# mbed_to_ccs.net
KiCad netlist of a schematic drawn in Altium Designer
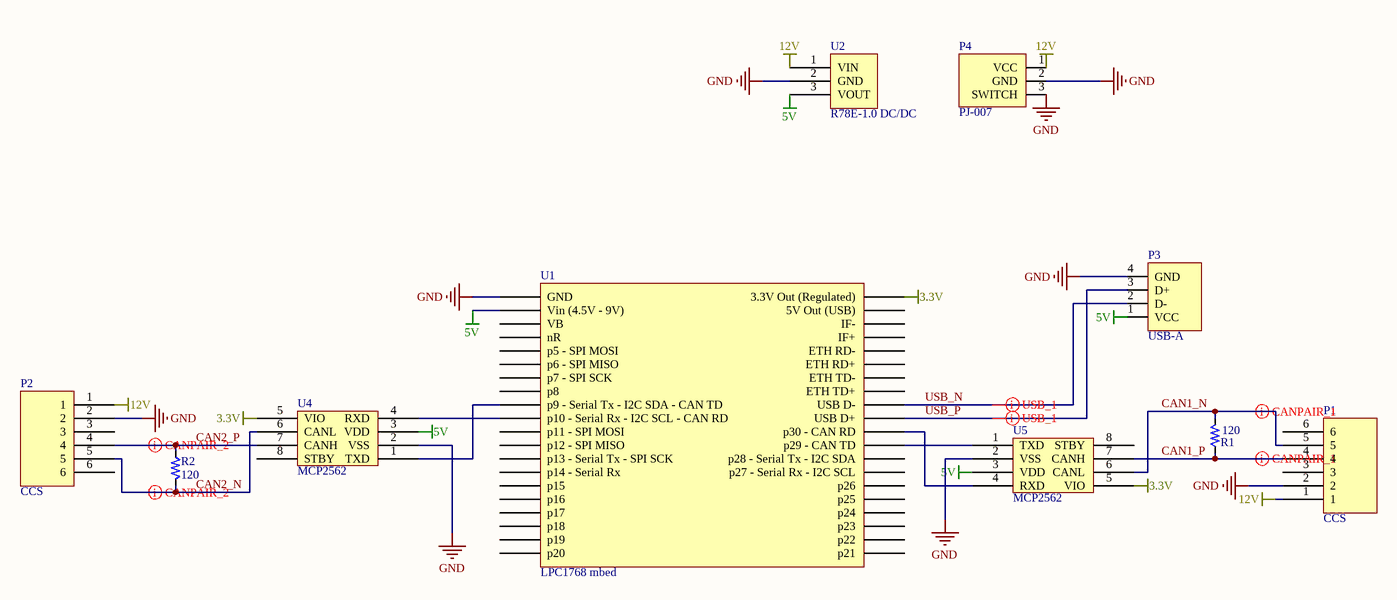
[diagram p0: mbed_to_ccs.SchDoc]

(export (version "E")
  (design (tool "Eeschema 10.0.6"))
  (components
    (comp (ref "P1")
      (value "CCS")
      (footprint "PCB_MLX_MICROFIT_3X2")
      (libsource (lib "") (part "SCH_MLX_MICROFIT_3X2_1"))
    )
    (comp (ref "P2")
      (value "CCS")
      (footprint "PCB_MLX_MICROFIT_3X2")
      (libsource (lib "SCH_MLX_MICROFIT_3X2_P") (part "SCH_MLX_MICROFIT_3X2"))
    )
    (comp (ref "P3")
      (value "USB-A")
      (footprint "USB-A UE27AC54100 Receptacle")
      (libsource (lib "USB-A UE27AC54100 Receptacle") (part "USB-A UE27AC54100 Receptacle"))
    )
    (comp (ref "P4")
      (value "PJ-007")
      (footprint "BARREL JACK PJ007")
      (libsource (lib "BARREL JACK PJ-007") (part "Component_1"))
    )
    (comp (ref "R1")
      (value "120")
      (footprint "PCB_GENERIC_SMD_0603")
      (description "120 Ohms")
      (libsource (lib "SCH_GENERIC_RESISTOR_0603") (part "SCH_GENERIC_RESISTOR_0603"))
    )
    (comp (ref "R2")
      (value "120")
      (footprint "PCB_GENERIC_SMD_0603")
      (description "120 Ohms")
      (libsource (lib "SCH_GENERIC_RESISTOR_0603") (part "SCH_GENERIC_RESISTOR_0603"))
    )
    (comp (ref "U1")
      (value "LPC1768 mbed")
      (footprint "LPC 1768 mbed Layout")
      (libsource (lib "LPC1768_mbed_SCH") (part "LPC1768 mbed"))
    )
    (comp (ref "U2")
      (value "R78E-1.0 DC/DC")
      (footprint "R78-1.0")
      (libsource (lib "R78E-1.0_DCDC_SCH") (part "R78E-1.0"))
    )
    (comp (ref "U4") (value "MCP2562") (footprint "MCP2562") (libsource (lib "") (part "MCP2562_1")))
    (comp (ref "U5") (value "MCP2562") (footprint "MCP2562") (libsource (lib "MCP2562_SCH") (part "MCP2562")))
  )
  (nets
    (net (code "1") (name "/CAN1_N") (class "Default")
      (node (ref "P1") (pin "5") (pinfunction "5_5") (pintype "passive"))
      (node (ref "R1") (pin "2") (pinfunction "2_2") (pintype "passive"))
      (node (ref "U5") (pin "6") (pinfunction "CANL_6") (pintype "passive"))
    )
    (net (code "2") (name "/CAN1_P") (class "Default")
      (node (ref "P1") (pin "4") (pinfunction "4_4") (pintype "passive"))
      (node (ref "R1") (pin "1") (pinfunction "1_1") (pintype "passive"))
      (node (ref "U5") (pin "7") (pinfunction "CANH_7") (pintype "passive"))
    )
    (net (code "3") (name "/CAN2_N") (class "Default")
      (node (ref "P2") (pin "5") (pinfunction "5_5") (pintype "passive"))
      (node (ref "R2") (pin "2") (pinfunction "2_2") (pintype "passive"))
      (node (ref "U4") (pin "6") (pinfunction "CANL_6") (pintype "passive"))
    )
    (net (code "4") (name "/CAN2_P") (class "Default")
      (node (ref "P2") (pin "4") (pinfunction "4_4") (pintype "passive"))
      (node (ref "R2") (pin "1") (pinfunction "1_1") (pintype "passive"))
      (node (ref "U4") (pin "7") (pinfunction "CANH_7") (pintype "passive"))
    )
    (net (code "5") (name "/USB_N") (class "Default")
      (node (ref "P3") (pin "2") (pinfunction "D-_2") (pintype "passive"))
      (node (ref "U1") (pin "32") (pinfunction "USB_D-_32") (pintype "passive"))
    )
    (net (code "6") (name "/USB_P") (class "Default")
      (node (ref "P3") (pin "3") (pinfunction "D+_3") (pintype "passive"))
      (node (ref "U1") (pin "31") (pinfunction "USB_D+_31") (pintype "passive"))
    )
    (net (code "7") (name "3.3V") (class "Default")
      (node (ref "U1") (pin "40") (pinfunction "3.3V_Out_(Regulated)_40") (pintype "passive"))
      (node (ref "U4") (pin "5") (pinfunction "VIO_5") (pintype "passive"))
      (node (ref "U5") (pin "5") (pinfunction "VIO_5") (pintype "passive"))
    )
    (net (code "8") (name "5V") (class "Default")
      (node (ref "P3") (pin "1") (pinfunction "VCC_1") (pintype "passive"))
      (node (ref "U1") (pin "2") (pinfunction "Vin_(4.5V_-_9V)_2") (pintype "passive"))
      (node (ref "U2") (pin "3") (pinfunction "VOUT_3") (pintype "passive"))
      (node (ref "U4") (pin "3") (pinfunction "VDD_3") (pintype "passive"))
      (node (ref "U5") (pin "3") (pinfunction "VDD_3") (pintype "passive"))
    )
    (net (code "9") (name "12V") (class "Default")
      (node (ref "P1") (pin "1") (pinfunction "1_1") (pintype "passive"))
      (node (ref "P2") (pin "1") (pinfunction "1_1") (pintype "passive"))
      (node (ref "P4") (pin "1") (pinfunction "VCC_1") (pintype "passive"))
      (node (ref "U2") (pin "1") (pinfunction "VIN_1") (pintype "passive"))
    )
    (net (code "10") (name "GND") (class "Default")
      (node (ref "P1") (pin "2") (pinfunction "2_2") (pintype "passive"))
      (node (ref "P2") (pin "2") (pinfunction "2_2") (pintype "passive"))
      (node (ref "P3") (pin "4") (pinfunction "GND_4") (pintype "passive"))
      (node (ref "P4") (pin "2") (pinfunction "GND_2") (pintype "passive"))
      (node (ref "P4") (pin "3") (pinfunction "SWITCH_3") (pintype "passive"))
      (node (ref "U1") (pin "1") (pinfunction "GND_1") (pintype "passive"))
      (node (ref "U2") (pin "2") (pinfunction "GND_2") (pintype "passive"))
      (node (ref "U4") (pin "2") (pinfunction "VSS_2") (pintype "passive"))
      (node (ref "U5") (pin "2") (pinfunction "VSS_2") (pintype "passive"))
    )
    (net (code "11") (name "Net-(U1-p9_-_Serial_Tx_-_I2C_SDA_-_CAN_TD)") (class "Default")
      (node (ref "U1") (pin "9") (pinfunction "p9_-_Serial_Tx_-_I2C_SDA_-_CAN_TD_9") (pintype "passive"))
      (node (ref "U4") (pin "1") (pinfunction "TXD_1") (pintype "passive"))
    )
    (net (code "12") (name "Net-(U1-p10_-_Serial_Rx_-_I2C_SCL_-_CAN_RD)") (class "Default")
      (node (ref "U1") (pin "10") (pinfunction "p10_-_Serial_Rx_-_I2C_SCL_-_CAN_RD_10") (pintype "passive"))
      (node (ref "U4") (pin "4") (pinfunction "RXD_4") (pintype "passive"))
    )
    (net (code "13") (name "Net-(U1-p29_-_CAN_TD)") (class "Default")
      (node (ref "U1") (pin "29") (pinfunction "p29_-_CAN_TD_29") (pintype "passive"))
      (node (ref "U5") (pin "1") (pinfunction "TXD_1") (pintype "passive"))
    )
    (net (code "14") (name "Net-(U1-p30_-_CAN_RD)") (class "Default")
      (node (ref "U1") (pin "30") (pinfunction "p30_-_CAN_RD_30") (pintype "passive"))
      (node (ref "U5") (pin "4") (pinfunction "RXD_4") (pintype "passive"))
    )
    (net (code "15") (name "unconnected-(P1-Pad3)") (class "Default")
      (node (ref "P1") (pin "3") (pinfunction "3_3") (pintype "passive"))
    )
    (net (code "16") (name "unconnected-(P1-Pad6)") (class "Default")
      (node (ref "P1") (pin "6") (pinfunction "6_6") (pintype "passive"))
    )
    (net (code "17") (name "unconnected-(P2-Pad3)") (class "Default")
      (node (ref "P2") (pin "3") (pinfunction "3_3") (pintype "passive"))
    )
    (net (code "18") (name "unconnected-(P2-Pad6)") (class "Default")
      (node (ref "P2") (pin "6") (pinfunction "6_6") (pintype "passive"))
    )
    (net (code "19") (name "unconnected-(U1-5V_Out_(USB)-Pad39)") (class "Default")
      (node (ref "U1") (pin "39") (pinfunction "5V_Out_(USB)_39") (pintype "passive"))
    )
    (net (code "20") (name "unconnected-(U1-ETH_RD+-Pad35)") (class "Default")
      (node (ref "U1") (pin "35") (pinfunction "ETH_RD+_35") (pintype "passive"))
    )
    (net (code "21") (name "unconnected-(U1-ETH_RD--Pad36)") (class "Default")
      (node (ref "U1") (pin "36") (pinfunction "ETH_RD-_36") (pintype "passive"))
    )
    (net (code "22") (name "unconnected-(U1-ETH_TD+-Pad33)") (class "Default")
      (node (ref "U1") (pin "33") (pinfunction "ETH_TD+_33") (pintype "passive"))
    )
    (net (code "23") (name "unconnected-(U1-ETH_TD--Pad34)") (class "Default")
      (node (ref "U1") (pin "34") (pinfunction "ETH_TD-_34") (pintype "passive"))
    )
    (net (code "24") (name "unconnected-(U1-IF+-Pad37)") (class "Default")
      (node (ref "U1") (pin "37") (pinfunction "IF+_37") (pintype "passive"))
    )
    (net (code "25") (name "unconnected-(U1-IF--Pad38)") (class "Default")
      (node (ref "U1") (pin "38") (pinfunction "IF-_38") (pintype "passive"))
    )
    (net (code "26") (name "unconnected-(U1-VB-Pad3)") (class "Default")
      (node (ref "U1") (pin "3") (pinfunction "VB_3") (pintype "passive"))
    )
    (net (code "27") (name "unconnected-(U1-nR-Pad4)") (class "Default")
      (node (ref "U1") (pin "4") (pinfunction "nR_4") (pintype "passive"))
    )
    (net (code "28") (name "unconnected-(U1-p5_-_SPI_MOSI-Pad5)") (class "Default")
      (node (ref "U1") (pin "5") (pinfunction "p5_-_SPI_MOSI_5") (pintype "passive"))
    )
    (net (code "29") (name "unconnected-(U1-p6_-_SPI_MISO-Pad6)") (class "Default")
      (node (ref "U1") (pin "6") (pinfunction "p6_-_SPI_MISO_6") (pintype "passive"))
    )
    (net (code "30") (name "unconnected-(U1-p7_-_SPI_SCK-Pad7)") (class "Default")
      (node (ref "U1") (pin "7") (pinfunction "p7_-_SPI_SCK_7") (pintype "passive"))
    )
    (net (code "31") (name "unconnected-(U1-p8-Pad8)") (class "Default")
      (node (ref "U1") (pin "8") (pinfunction "p8_8") (pintype "passive"))
    )
    (net (code "32") (name "unconnected-(U1-p11_-_SPI_MOSI-Pad11)") (class "Default")
      (node (ref "U1") (pin "11") (pinfunction "p11_-_SPI_MOSI_11") (pintype "passive"))
    )
    (net (code "33") (name "unconnected-(U1-p12_-_SPI_MISO-Pad12)") (class "Default")
      (node (ref "U1") (pin "12") (pinfunction "p12_-_SPI_MISO_12") (pintype "passive"))
    )
    (net (code "34") (name "unconnected-(U1-p13_-_Serial_Tx_-_SPI_SCK-Pad13)") (class "Default")
      (node (ref "U1") (pin "13") (pinfunction "p13_-_Serial_Tx_-_SPI_SCK_13") (pintype "passive"))
    )
    (net (code "35") (name "unconnected-(U1-p14_-_Serial_Rx-Pad14)") (class "Default")
      (node (ref "U1") (pin "14") (pinfunction "p14_-_Serial_Rx_14") (pintype "passive"))
    )
    (net (code "36") (name "unconnected-(U1-p15-Pad15)") (class "Default")
      (node (ref "U1") (pin "15") (pinfunction "p15_15") (pintype "passive"))
    )
    (net (code "37") (name "unconnected-(U1-p16-Pad16)") (class "Default")
      (node (ref "U1") (pin "16") (pinfunction "p16_16") (pintype "passive"))
    )
    (net (code "38") (name "unconnected-(U1-p17-Pad17)") (class "Default")
      (node (ref "U1") (pin "17") (pinfunction "p17_17") (pintype "passive"))
    )
    (net (code "39") (name "unconnected-(U1-p18-Pad18)") (class "Default")
      (node (ref "U1") (pin "18") (pinfunction "p18_18") (pintype "passive"))
    )
    (net (code "40") (name "unconnected-(U1-p19-Pad19)") (class "Default")
      (node (ref "U1") (pin "19") (pinfunction "p19_19") (pintype "passive"))
    )
    (net (code "41") (name "unconnected-(U1-p20-Pad20)") (class "Default")
      (node (ref "U1") (pin "20") (pinfunction "p20_20") (pintype "passive"))
    )
    (net (code "42") (name "unconnected-(U1-p21-Pad21)") (class "Default")
      (node (ref "U1") (pin "21") (pinfunction "p21_21") (pintype "passive"))
    )
    (net (code "43") (name "unconnected-(U1-p22-Pad22)") (class "Default")
      (node (ref "U1") (pin "22") (pinfunction "p22_22") (pintype "passive"))
    )
    (net (code "44") (name "unconnected-(U1-p23-Pad23)") (class "Default")
      (node (ref "U1") (pin "23") (pinfunction "p23_23") (pintype "passive"))
    )
    (net (code "45") (name "unconnected-(U1-p24-Pad24)") (class "Default")
      (node (ref "U1") (pin "24") (pinfunction "p24_24") (pintype "passive"))
    )
    (net (code "46") (name "unconnected-(U1-p25-Pad25)") (class "Default")
      (node (ref "U1") (pin "25") (pinfunction "p25_25") (pintype "passive"))
    )
    (net (code "47") (name "unconnected-(U1-p26-Pad26)") (class "Default")
      (node (ref "U1") (pin "26") (pinfunction "p26_26") (pintype "passive"))
    )
    (net (code "48") (name "unconnected-(U1-p27_-_Serial_Rx_-_I2C_SCL-Pad27)") (class "Default")
      (node (ref "U1") (pin "27") (pinfunction "p27_-_Serial_Rx_-_I2C_SCL_27") (pintype "passive"))
    )
    (net (code "49") (name "unconnected-(U1-p28_-_Serial_Tx_-_I2C_SDA-Pad28)") (class "Default")
      (node (ref "U1") (pin "28") (pinfunction "p28_-_Serial_Tx_-_I2C_SDA_28") (pintype "passive"))
    )
    (net (code "50") (name "unconnected-(U4-STBY-Pad8)") (class "Default")
      (node (ref "U4") (pin "8") (pinfunction "STBY_8") (pintype "passive"))
    )
    (net (code "51") (name "unconnected-(U5-STBY-Pad8)") (class "Default")
      (node (ref "U5") (pin "8") (pinfunction "STBY_8") (pintype "passive"))
    )
  )
)
